# M2S-v2-Modular.net
KiCad netlist of a schematic drawn in EAGLE
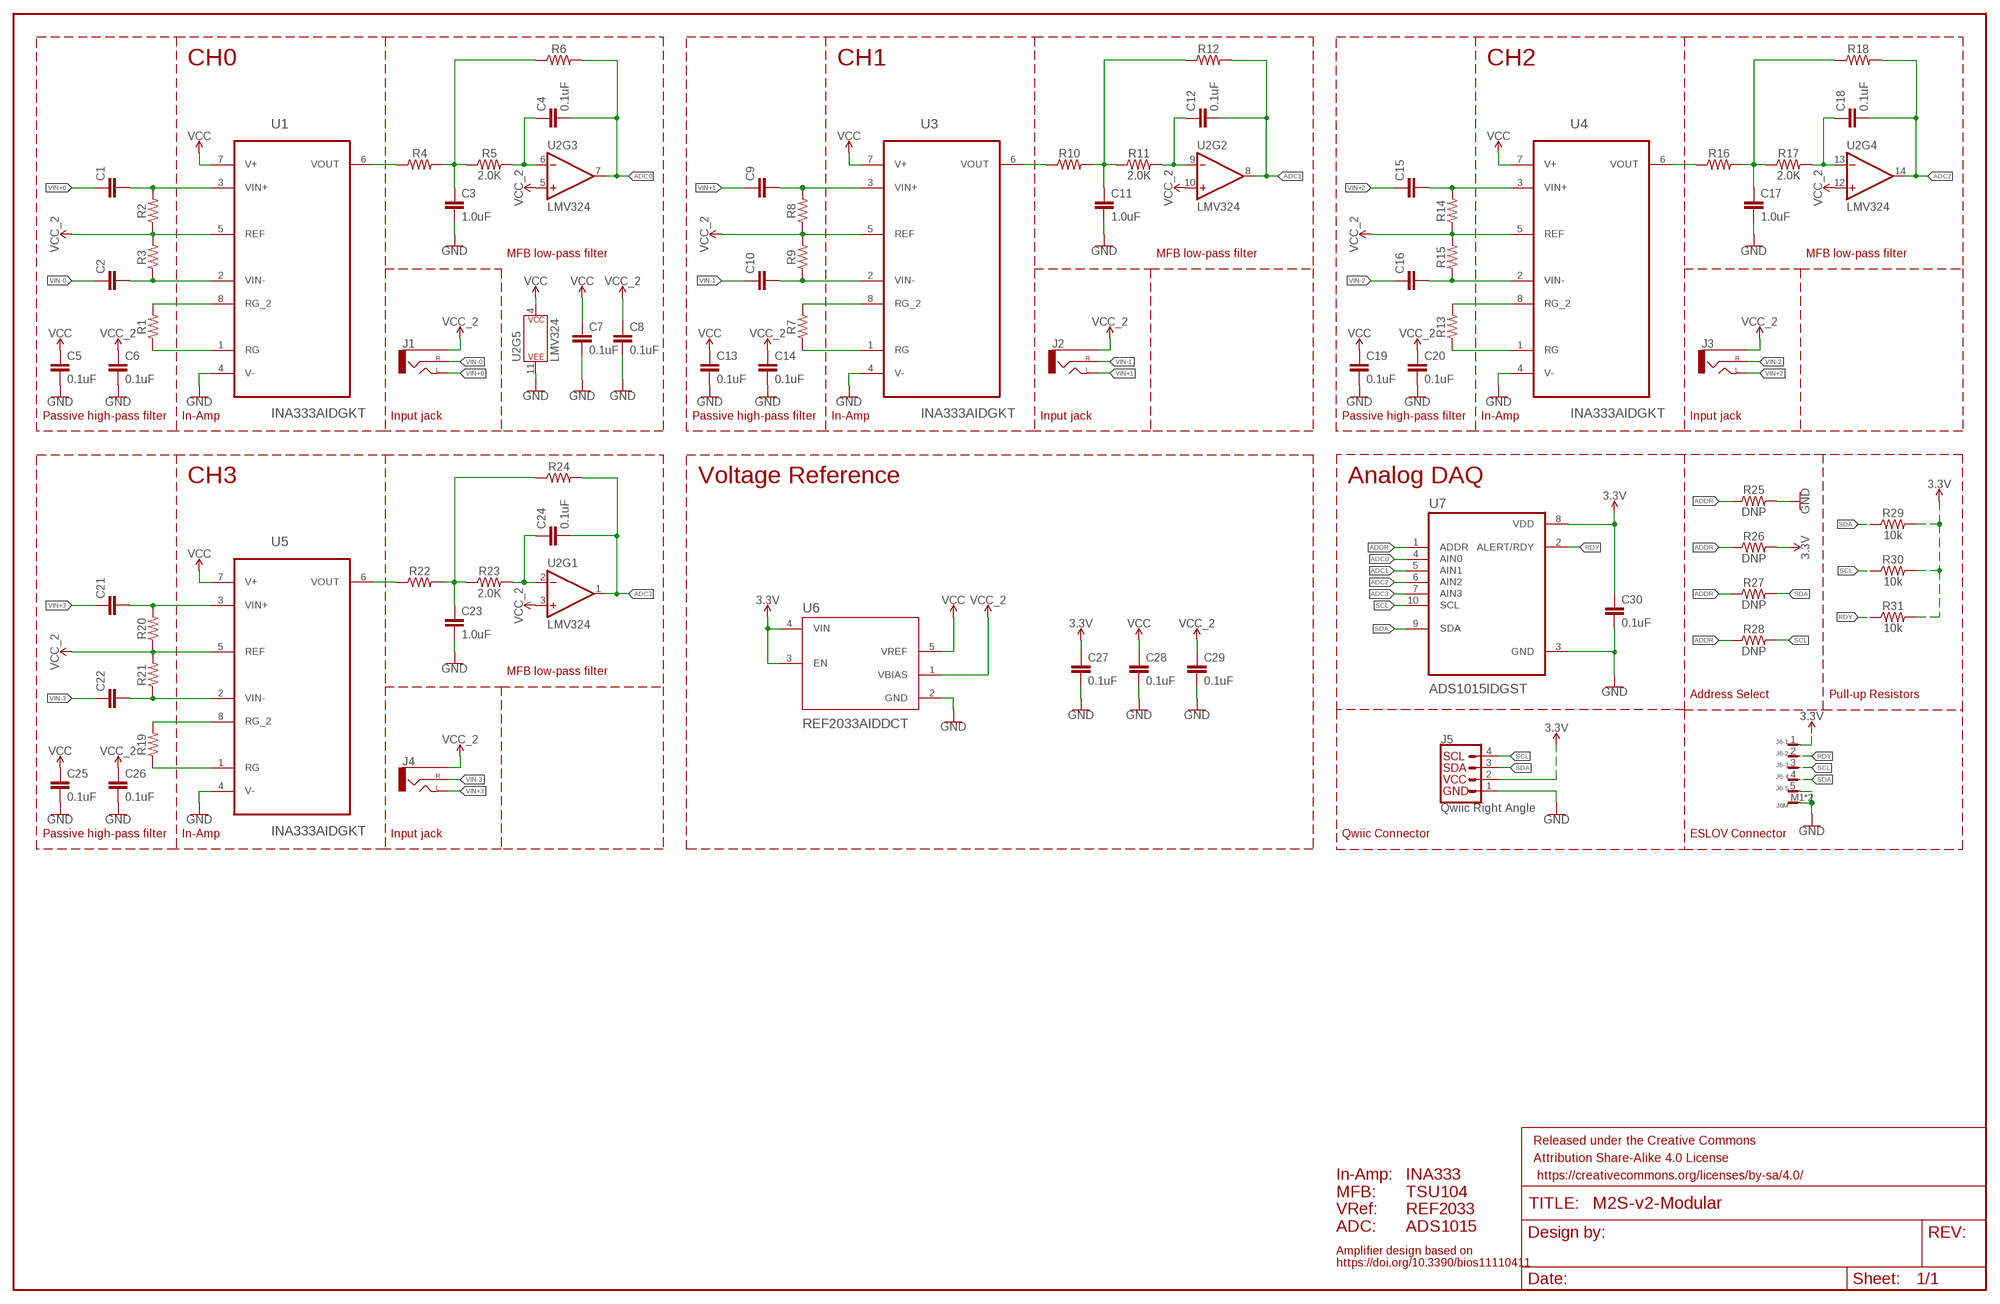
[diagram p0: schematic, sheet 1]

(export (version "E")
  (design (tool "Eeschema 10.0.6"))
  (components
    (comp (ref "C1")
      (value "0.22uF")
      (footprint "eagle-import:0402")
      (libsource (lib "eagle-import") (part "CAP-0402"))
    )
    (comp (ref "C2")
      (value "0.22uF")
      (footprint "eagle-import:0402")
      (libsource (lib "eagle-import") (part "CAP-0402"))
    )
    (comp (ref "C3")
      (value "1.0uF")
      (footprint "eagle-import:0402")
      (libsource (lib "eagle-import") (part "1.0UF-0402-16V-10%"))
    )
    (comp (ref "C4")
      (value "0.1uF")
      (footprint "eagle-import:0402")
      (libsource (lib "eagle-import") (part "0.1UF-0402-6.3V-10%-X7R"))
    )
    (comp (ref "C5")
      (value "0.1uF")
      (footprint "eagle-import:0402")
      (libsource (lib "eagle-import") (part "0.1UF-0402-6.3V-10%-X7R"))
    )
    (comp (ref "C6")
      (value "0.1uF")
      (footprint "eagle-import:0402")
      (libsource (lib "eagle-import") (part "0.1UF-0402-6.3V-10%-X7R"))
    )
    (comp (ref "C7")
      (value "0.1uF")
      (footprint "eagle-import:0402")
      (libsource (lib "eagle-import") (part "0.1UF-0402-6.3V-10%-X7R"))
    )
    (comp (ref "C8")
      (value "0.1uF")
      (footprint "eagle-import:0402")
      (libsource (lib "eagle-import") (part "0.1UF-0402-6.3V-10%-X7R"))
    )
    (comp (ref "C9")
      (value "0.22uF")
      (footprint "eagle-import:0402")
      (libsource (lib "eagle-import") (part "CAP-0402"))
    )
    (comp (ref "C10")
      (value "0.22uF")
      (footprint "eagle-import:0402")
      (libsource (lib "eagle-import") (part "CAP-0402"))
    )
    (comp (ref "C11")
      (value "1.0uF")
      (footprint "eagle-import:0402")
      (libsource (lib "eagle-import") (part "1.0UF-0402-16V-10%"))
    )
    (comp (ref "C12")
      (value "0.1uF")
      (footprint "eagle-import:0402")
      (libsource (lib "eagle-import") (part "0.1UF-0402-6.3V-10%-X7R"))
    )
    (comp (ref "C13")
      (value "0.1uF")
      (footprint "eagle-import:0402")
      (libsource (lib "eagle-import") (part "0.1UF-0402-6.3V-10%-X7R"))
    )
    (comp (ref "C14")
      (value "0.1uF")
      (footprint "eagle-import:0402")
      (libsource (lib "eagle-import") (part "0.1UF-0402-6.3V-10%-X7R"))
    )
    (comp (ref "C15")
      (value "0.22uF")
      (footprint "eagle-import:0402")
      (libsource (lib "eagle-import") (part "CAP-0402"))
    )
    (comp (ref "C16")
      (value "0.22uF")
      (footprint "eagle-import:0402")
      (libsource (lib "eagle-import") (part "CAP-0402"))
    )
    (comp (ref "C17")
      (value "1.0uF")
      (footprint "eagle-import:0402")
      (libsource (lib "eagle-import") (part "1.0UF-0402-16V-10%"))
    )
    (comp (ref "C18")
      (value "0.1uF")
      (footprint "eagle-import:0402")
      (libsource (lib "eagle-import") (part "0.1UF-0402-6.3V-10%-X7R"))
    )
    (comp (ref "C19")
      (value "0.1uF")
      (footprint "eagle-import:0402")
      (libsource (lib "eagle-import") (part "0.1UF-0402-6.3V-10%-X7R"))
    )
    (comp (ref "C20")
      (value "0.1uF")
      (footprint "eagle-import:0402")
      (libsource (lib "eagle-import") (part "0.1UF-0402-6.3V-10%-X7R"))
    )
    (comp (ref "C21")
      (value "0.22uF")
      (footprint "eagle-import:0402")
      (libsource (lib "eagle-import") (part "CAP-0402"))
    )
    (comp (ref "C22")
      (value "0.22uF")
      (footprint "eagle-import:0402")
      (libsource (lib "eagle-import") (part "CAP-0402"))
    )
    (comp (ref "C23")
      (value "1.0uF")
      (footprint "eagle-import:0402")
      (libsource (lib "eagle-import") (part "1.0UF-0402-16V-10%"))
    )
    (comp (ref "C24")
      (value "0.1uF")
      (footprint "eagle-import:0402")
      (libsource (lib "eagle-import") (part "0.1UF-0402-6.3V-10%-X7R"))
    )
    (comp (ref "C25")
      (value "0.1uF")
      (footprint "eagle-import:0402")
      (libsource (lib "eagle-import") (part "0.1UF-0402-6.3V-10%-X7R"))
    )
    (comp (ref "C26")
      (value "0.1uF")
      (footprint "eagle-import:0402")
      (libsource (lib "eagle-import") (part "0.1UF-0402-6.3V-10%-X7R"))
    )
    (comp (ref "C27")
      (value "0.1uF")
      (footprint "eagle-import:0402")
      (libsource (lib "eagle-import") (part "0.1UF-0402-6.3V-10%-X7R"))
    )
    (comp (ref "C28")
      (value "0.1uF")
      (footprint "eagle-import:0402")
      (libsource (lib "eagle-import") (part "0.1UF-0402-6.3V-10%-X7R"))
    )
    (comp (ref "C29")
      (value "0.1uF")
      (footprint "eagle-import:0402")
      (libsource (lib "eagle-import") (part "0.1UF-0402-6.3V-10%-X7R"))
    )
    (comp (ref "C30")
      (value "0.1uF")
      (footprint "eagle-import:0402")
      (libsource (lib "eagle-import") (part "0.1UF-0402-6.3V-10%-X7R"))
    )
    (comp (ref "FRAME1")
      (value "FRAME-LEDGERNO_FOOTPRINT")
      (footprint "eagle-import:DUMMY")
      (libsource (lib "eagle-import") (part "FRAME-LEDGERNO_FOOTPRINT"))
    )
    (comp (ref "J1")
      (value "AUDIO_JACK_2.5MM_2.5MM")
      (footprint "eagle-import:STEREOJACK2.5MM_STEREOJACK2.5MM")
      (libsource (lib "eagle-import") (part "AUDIO_JACK_2.5MM_2.5MM"))
    )
    (comp (ref "J2")
      (value "AUDIO_JACK_2.5MM_2.5MM")
      (footprint "eagle-import:STEREOJACK2.5MM_STEREOJACK2.5MM")
      (libsource (lib "eagle-import") (part "AUDIO_JACK_2.5MM_2.5MM"))
    )
    (comp (ref "J3")
      (value "AUDIO_JACK_2.5MM_2.5MM")
      (footprint "eagle-import:STEREOJACK2.5MM_STEREOJACK2.5MM")
      (libsource (lib "eagle-import") (part "AUDIO_JACK_2.5MM_2.5MM"))
    )
    (comp (ref "J4")
      (value "AUDIO_JACK_2.5MM_2.5MM")
      (footprint "eagle-import:STEREOJACK2.5MM_STEREOJACK2.5MM")
      (libsource (lib "eagle-import") (part "AUDIO_JACK_2.5MM_2.5MM"))
    )
    (comp (ref "J5")
      (value "Qwiic Right Angle")
      (footprint "eagle-import:JST04_1MM_RA")
      (libsource (lib "eagle-import") (part "I2C_STANDARDQWIIC"))
    )
    (comp (ref "J6")
      (value "SM05B-SRSS-TB")
      (footprint "eagle-import:SM05B-SRSS-TB")
      (libsource (lib "eagle-import") (part "SM05B-SRSS-TB"))
    )
    (comp (ref "R1")
      (value "1KOHM-0402-1/16W-1%")
      (footprint "eagle-import:0402")
      (libsource (lib "eagle-import") (part "1KOHM-0402-1/16W-1%"))
    )
    (comp (ref "R2")
      (value "RESISTOR0402")
      (footprint "eagle-import:0402")
      (libsource (lib "eagle-import") (part "RESISTOR0402"))
    )
    (comp (ref "R3")
      (value "RESISTOR0402")
      (footprint "eagle-import:0402")
      (libsource (lib "eagle-import") (part "RESISTOR0402"))
    )
    (comp (ref "R4")
      (value "RESISTOR0402")
      (footprint "eagle-import:0402")
      (libsource (lib "eagle-import") (part "RESISTOR0402"))
    )
    (comp (ref "R5")
      (value "2.0K")
      (footprint "eagle-import:0402")
      (libsource (lib "eagle-import") (part "2.0KOHM-0402-1/16W-1%"))
    )
    (comp (ref "R6")
      (value "RESISTOR0402")
      (footprint "eagle-import:0402")
      (libsource (lib "eagle-import") (part "RESISTOR0402"))
    )
    (comp (ref "R7")
      (value "1KOHM-0402-1/16W-1%")
      (footprint "eagle-import:0402")
      (libsource (lib "eagle-import") (part "1KOHM-0402-1/16W-1%"))
    )
    (comp (ref "R8")
      (value "RESISTOR0402")
      (footprint "eagle-import:0402")
      (libsource (lib "eagle-import") (part "RESISTOR0402"))
    )
    (comp (ref "R9")
      (value "RESISTOR0402")
      (footprint "eagle-import:0402")
      (libsource (lib "eagle-import") (part "RESISTOR0402"))
    )
    (comp (ref "R10")
      (value "RESISTOR0402")
      (footprint "eagle-import:0402")
      (libsource (lib "eagle-import") (part "RESISTOR0402"))
    )
    (comp (ref "R11")
      (value "2.0K")
      (footprint "eagle-import:0402")
      (libsource (lib "eagle-import") (part "2.0KOHM-0402-1/16W-1%"))
    )
    (comp (ref "R12")
      (value "RESISTOR0402")
      (footprint "eagle-import:0402")
      (libsource (lib "eagle-import") (part "RESISTOR0402"))
    )
    (comp (ref "R13")
      (value "1KOHM-0402-1/16W-1%")
      (footprint "eagle-import:0402")
      (libsource (lib "eagle-import") (part "1KOHM-0402-1/16W-1%"))
    )
    (comp (ref "R14")
      (value "RESISTOR0402")
      (footprint "eagle-import:0402")
      (libsource (lib "eagle-import") (part "RESISTOR0402"))
    )
    (comp (ref "R15")
      (value "RESISTOR0402")
      (footprint "eagle-import:0402")
      (libsource (lib "eagle-import") (part "RESISTOR0402"))
    )
    (comp (ref "R16")
      (value "RESISTOR0402")
      (footprint "eagle-import:0402")
      (libsource (lib "eagle-import") (part "RESISTOR0402"))
    )
    (comp (ref "R17")
      (value "2.0K")
      (footprint "eagle-import:0402")
      (libsource (lib "eagle-import") (part "2.0KOHM-0402-1/16W-1%"))
    )
    (comp (ref "R18")
      (value "RESISTOR0402")
      (footprint "eagle-import:0402")
      (libsource (lib "eagle-import") (part "RESISTOR0402"))
    )
    (comp (ref "R19")
      (value "1KOHM-0402-1/16W-1%")
      (footprint "eagle-import:0402")
      (libsource (lib "eagle-import") (part "1KOHM-0402-1/16W-1%"))
    )
    (comp (ref "R20")
      (value "RESISTOR0402")
      (footprint "eagle-import:0402")
      (libsource (lib "eagle-import") (part "RESISTOR0402"))
    )
    (comp (ref "R21")
      (value "RESISTOR0402")
      (footprint "eagle-import:0402")
      (libsource (lib "eagle-import") (part "RESISTOR0402"))
    )
    (comp (ref "R22")
      (value "RESISTOR0402")
      (footprint "eagle-import:0402")
      (libsource (lib "eagle-import") (part "RESISTOR0402"))
    )
    (comp (ref "R23")
      (value "2.0K")
      (footprint "eagle-import:0402")
      (libsource (lib "eagle-import") (part "2.0KOHM-0402-1/16W-1%"))
    )
    (comp (ref "R24")
      (value "RESISTOR0402")
      (footprint "eagle-import:0402")
      (libsource (lib "eagle-import") (part "RESISTOR0402"))
    )
    (comp (ref "R25")
      (value "DNP")
      (footprint "eagle-import:0402")
      (libsource (lib "eagle-import") (part "DNP-0402"))
    )
    (comp (ref "R26")
      (value "DNP")
      (footprint "eagle-import:0402")
      (libsource (lib "eagle-import") (part "DNP-0402"))
    )
    (comp (ref "R27")
      (value "DNP")
      (footprint "eagle-import:0402")
      (libsource (lib "eagle-import") (part "DNP-0402"))
    )
    (comp (ref "R28")
      (value "DNP")
      (footprint "eagle-import:0402")
      (libsource (lib "eagle-import") (part "DNP-0402"))
    )
    (comp (ref "R29")
      (value "10k")
      (footprint "eagle-import:0402")
      (libsource (lib "eagle-import") (part "10KOHM-0402-1/16W-1%"))
    )
    (comp (ref "R30")
      (value "10k")
      (footprint "eagle-import:0402")
      (libsource (lib "eagle-import") (part "10KOHM-0402-1/16W-1%"))
    )
    (comp (ref "R31")
      (value "10k")
      (footprint "eagle-import:0402")
      (libsource (lib "eagle-import") (part "10KOHM-0402-1/16W-1%"))
    )
    (comp (ref "U1")
      (value "INA333AIDGKT")
      (footprint "eagle-import:SOP65P490X110-8N")
      (libsource (lib "eagle-import") (part "INA333AIDGKT"))
    )
    (comp (ref "U2")
      (value "LMV324")
      (footprint "eagle-import:SO14")
      (libsource (lib "eagle-import") (part "LMV324"))
    )
    (comp (ref "U3")
      (value "INA333AIDGKT")
      (footprint "eagle-import:SOP65P490X110-8N")
      (libsource (lib "eagle-import") (part "INA333AIDGKT"))
    )
    (comp (ref "U4")
      (value "INA333AIDGKT")
      (footprint "eagle-import:SOP65P490X110-8N")
      (libsource (lib "eagle-import") (part "INA333AIDGKT"))
    )
    (comp (ref "U5")
      (value "INA333AIDGKT")
      (footprint "eagle-import:SOP65P490X110-8N")
      (libsource (lib "eagle-import") (part "INA333AIDGKT"))
    )
    (comp (ref "U6")
      (value "REF2033AIDDCT")
      (footprint "eagle-import:SOT95P280X110-5N")
      (fields (field (name "MF") "Texas Instruments"))
      (libsource (lib "eagle-import") (part "REF2033AIDDCT"))
    )
    (comp (ref "U7")
      (value "ADS1015IDGST")
      (footprint "eagle-import:SOP50P490X110-10N")
      (fields (field (name "MF") "Texas Instruments"))
      (libsource (lib "eagle-import") (part "ADS1015IDGST"))
    )
  )
  (nets
    (net (code "1") (name "3.3V") (class "Default")
      (node (ref "C27") (pin "1") (pinfunction "1_1") (pintype "passive"))
      (node (ref "C30") (pin "1") (pinfunction "1_1") (pintype "passive"))
      (node (ref "J5") (pin "2") (pinfunction "2_2") (pintype "power_in"))
      (node (ref "J6") (pin "1") (pinfunction "P_1") (pintype "bidirectional"))
      (node (ref "R26") (pin "2") (pinfunction "2_2") (pintype "passive"))
      (node (ref "R29") (pin "2") (pinfunction "2_2") (pintype "passive"))
      (node (ref "R30") (pin "2") (pinfunction "2_2") (pintype "passive"))
      (node (ref "R31") (pin "2") (pinfunction "2_2") (pintype "passive"))
      (node (ref "U6") (pin "3") (pinfunction "EN_3") (pintype "input"))
      (node (ref "U6") (pin "4") (pinfunction "VIN_4") (pintype "power_in"))
      (node (ref "U7") (pin "8") (pinfunction "VDD_8") (pintype "power_in"))
    )
    (net (code "2") (name "ADC0") (class "Default")
      (node (ref "C4") (pin "2") (pinfunction "2_2") (pintype "passive"))
      (node (ref "R6") (pin "2") (pinfunction "2_2") (pintype "passive"))
      (node (ref "U2") (pin "7") (pinfunction "OUT_7") (pintype "output"))
      (node (ref "U7") (pin "4") (pinfunction "AIN0_4") (pintype "input"))
    )
    (net (code "3") (name "ADC1") (class "Default")
      (node (ref "C12") (pin "2") (pinfunction "2_2") (pintype "passive"))
      (node (ref "R12") (pin "2") (pinfunction "2_2") (pintype "passive"))
      (node (ref "U2") (pin "8") (pinfunction "OUT_8") (pintype "output"))
      (node (ref "U7") (pin "5") (pinfunction "AIN1_5") (pintype "input"))
    )
    (net (code "4") (name "ADC2") (class "Default")
      (node (ref "C18") (pin "2") (pinfunction "2_2") (pintype "passive"))
      (node (ref "R18") (pin "2") (pinfunction "2_2") (pintype "passive"))
      (node (ref "U2") (pin "14") (pinfunction "OUT_14") (pintype "output"))
      (node (ref "U7") (pin "6") (pinfunction "AIN2_6") (pintype "input"))
    )
    (net (code "5") (name "ADC3") (class "Default")
      (node (ref "C24") (pin "2") (pinfunction "2_2") (pintype "passive"))
      (node (ref "R24") (pin "2") (pinfunction "2_2") (pintype "passive"))
      (node (ref "U2") (pin "1") (pinfunction "OUT_1") (pintype "output"))
      (node (ref "U7") (pin "7") (pinfunction "AIN3_7") (pintype "input"))
    )
    (net (code "6") (name "ADDR") (class "Default")
      (node (ref "R25") (pin "1") (pinfunction "1_1") (pintype "passive"))
      (node (ref "R26") (pin "1") (pinfunction "1_1") (pintype "passive"))
      (node (ref "R27") (pin "1") (pinfunction "1_1") (pintype "passive"))
      (node (ref "R28") (pin "1") (pinfunction "1_1") (pintype "passive"))
      (node (ref "U7") (pin "1") (pinfunction "ADDR_1") (pintype "input"))
    )
    (net (code "7") (name "GND") (class "Default")
      (node (ref "C11") (pin "2") (pinfunction "2_2") (pintype "passive"))
      (node (ref "C13") (pin "2") (pinfunction "2_2") (pintype "passive"))
      (node (ref "C14") (pin "2") (pinfunction "2_2") (pintype "passive"))
      (node (ref "C17") (pin "2") (pinfunction "2_2") (pintype "passive"))
      (node (ref "C19") (pin "2") (pinfunction "2_2") (pintype "passive"))
      (node (ref "C20") (pin "2") (pinfunction "2_2") (pintype "passive"))
      (node (ref "C23") (pin "2") (pinfunction "2_2") (pintype "passive"))
      (node (ref "C25") (pin "2") (pinfunction "2_2") (pintype "passive"))
      (node (ref "C26") (pin "2") (pinfunction "2_2") (pintype "passive"))
      (node (ref "C27") (pin "2") (pinfunction "2_2") (pintype "passive"))
      (node (ref "C28") (pin "2") (pinfunction "2_2") (pintype "passive"))
      (node (ref "C29") (pin "2") (pinfunction "2_2") (pintype "passive"))
      (node (ref "C3") (pin "2") (pinfunction "2_2") (pintype "passive"))
      (node (ref "C30") (pin "2") (pinfunction "2_2") (pintype "passive"))
      (node (ref "C5") (pin "2") (pinfunction "2_2") (pintype "passive"))
      (node (ref "C6") (pin "2") (pinfunction "2_2") (pintype "passive"))
      (node (ref "C7") (pin "2") (pinfunction "2_2") (pintype "passive"))
      (node (ref "C8") (pin "2") (pinfunction "2_2") (pintype "passive"))
      (node (ref "J5") (pin "1") (pinfunction "1_1") (pintype "power_in"))
      (node (ref "J6") (pin "5") (pinfunction "P_5") (pintype "bidirectional"))
      (node (ref "J6") (pin "M1") (pinfunction "P_M1") (pintype "bidirectional"))
      (node (ref "J6") (pin "M2") (pinfunction "P_M2") (pintype "bidirectional"))
      (node (ref "R25") (pin "2") (pinfunction "2_2") (pintype "passive"))
      (node (ref "U1") (pin "4") (pinfunction "V-_4") (pintype "power_in"))
      (node (ref "U2") (pin "11") (pinfunction "P$V-_11") (pintype "bidirectional"))
      (node (ref "U3") (pin "4") (pinfunction "V-_4") (pintype "power_in"))
      (node (ref "U4") (pin "4") (pinfunction "V-_4") (pintype "power_in"))
      (node (ref "U5") (pin "4") (pinfunction "V-_4") (pintype "power_in"))
      (node (ref "U6") (pin "2") (pinfunction "GND_2") (pintype "power_in"))
      (node (ref "U7") (pin "3") (pinfunction "GND_3") (pintype "power_in"))
    )
    (net (code "8") (name "Net-(C3-Pad1)") (class "Default")
      (node (ref "C3") (pin "1") (pinfunction "1_1") (pintype "passive"))
      (node (ref "R4") (pin "2") (pinfunction "2_2") (pintype "passive"))
      (node (ref "R5") (pin "1") (pinfunction "1_1") (pintype "passive"))
      (node (ref "R6") (pin "1") (pinfunction "1_1") (pintype "passive"))
    )
    (net (code "9") (name "Net-(C11-Pad1)") (class "Default")
      (node (ref "C11") (pin "1") (pinfunction "1_1") (pintype "passive"))
      (node (ref "R10") (pin "2") (pinfunction "2_2") (pintype "passive"))
      (node (ref "R11") (pin "1") (pinfunction "1_1") (pintype "passive"))
      (node (ref "R12") (pin "1") (pinfunction "1_1") (pintype "passive"))
    )
    (net (code "10") (name "Net-(C17-Pad1)") (class "Default")
      (node (ref "C17") (pin "1") (pinfunction "1_1") (pintype "passive"))
      (node (ref "R16") (pin "2") (pinfunction "2_2") (pintype "passive"))
      (node (ref "R17") (pin "1") (pinfunction "1_1") (pintype "passive"))
      (node (ref "R18") (pin "1") (pinfunction "1_1") (pintype "passive"))
    )
    (net (code "11") (name "Net-(C23-Pad1)") (class "Default")
      (node (ref "C23") (pin "1") (pinfunction "1_1") (pintype "passive"))
      (node (ref "R22") (pin "2") (pinfunction "2_2") (pintype "passive"))
      (node (ref "R23") (pin "1") (pinfunction "1_1") (pintype "passive"))
      (node (ref "R24") (pin "1") (pinfunction "1_1") (pintype "passive"))
    )
    (net (code "12") (name "Net-(U1-RG)") (class "Default")
      (node (ref "R1") (pin "1") (pinfunction "1_1") (pintype "passive"))
      (node (ref "U1") (pin "1") (pinfunction "RG_1") (pintype "passive"))
    )
    (net (code "13") (name "Net-(U1-RG_2)") (class "Default")
      (node (ref "R1") (pin "2") (pinfunction "2_2") (pintype "passive"))
      (node (ref "U1") (pin "8") (pinfunction "RG_2_8") (pintype "passive"))
    )
    (net (code "14") (name "Net-(U1-VIN+)") (class "Default")
      (node (ref "C1") (pin "2") (pinfunction "2_2") (pintype "passive"))
      (node (ref "R2") (pin "2") (pinfunction "2_2") (pintype "passive"))
      (node (ref "U1") (pin "3") (pinfunction "VIN+_3") (pintype "input"))
    )
    (net (code "15") (name "Net-(U1-VIN-)") (class "Default")
      (node (ref "C2") (pin "2") (pinfunction "2_2") (pintype "passive"))
      (node (ref "R3") (pin "1") (pinfunction "1_1") (pintype "passive"))
      (node (ref "U1") (pin "2") (pinfunction "VIN-_2") (pintype "input"))
    )
    (net (code "16") (name "Net-(U1-VOUT)") (class "Default")
      (node (ref "R4") (pin "1") (pinfunction "1_1") (pintype "passive"))
      (node (ref "U1") (pin "6") (pinfunction "VOUT_6") (pintype "output"))
    )
    (net (code "17") (name "Net-(U2A--IN)") (class "Default")
      (node (ref "C24") (pin "1") (pinfunction "1_1") (pintype "passive"))
      (node (ref "R23") (pin "2") (pinfunction "2_2") (pintype "passive"))
      (node (ref "U2") (pin "2") (pinfunction "-IN_2") (pintype "input"))
    )
    (net (code "18") (name "Net-(U2B--IN)") (class "Default")
      (node (ref "C12") (pin "1") (pinfunction "1_1") (pintype "passive"))
      (node (ref "R11") (pin "2") (pinfunction "2_2") (pintype "passive"))
      (node (ref "U2") (pin "9") (pinfunction "-IN_9") (pintype "input"))
    )
    (net (code "19") (name "Net-(U2C--IN)") (class "Default")
      (node (ref "C4") (pin "1") (pinfunction "1_1") (pintype "passive"))
      (node (ref "R5") (pin "2") (pinfunction "2_2") (pintype "passive"))
      (node (ref "U2") (pin "6") (pinfunction "-IN_6") (pintype "input"))
    )
    (net (code "20") (name "Net-(U2D--IN)") (class "Default")
      (node (ref "C18") (pin "1") (pinfunction "1_1") (pintype "passive"))
      (node (ref "R17") (pin "2") (pinfunction "2_2") (pintype "passive"))
      (node (ref "U2") (pin "13") (pinfunction "-IN_13") (pintype "input"))
    )
    (net (code "21") (name "Net-(U3-RG)") (class "Default")
      (node (ref "R7") (pin "1") (pinfunction "1_1") (pintype "passive"))
      (node (ref "U3") (pin "1") (pinfunction "RG_1") (pintype "passive"))
    )
    (net (code "22") (name "Net-(U3-RG_2)") (class "Default")
      (node (ref "R7") (pin "2") (pinfunction "2_2") (pintype "passive"))
      (node (ref "U3") (pin "8") (pinfunction "RG_2_8") (pintype "passive"))
    )
    (net (code "23") (name "Net-(U3-VIN+)") (class "Default")
      (node (ref "C9") (pin "2") (pinfunction "2_2") (pintype "passive"))
      (node (ref "R8") (pin "2") (pinfunction "2_2") (pintype "passive"))
      (node (ref "U3") (pin "3") (pinfunction "VIN+_3") (pintype "input"))
    )
    (net (code "24") (name "Net-(U3-VIN-)") (class "Default")
      (node (ref "C10") (pin "2") (pinfunction "2_2") (pintype "passive"))
      (node (ref "R9") (pin "1") (pinfunction "1_1") (pintype "passive"))
      (node (ref "U3") (pin "2") (pinfunction "VIN-_2") (pintype "input"))
    )
    (net (code "25") (name "Net-(U3-VOUT)") (class "Default")
      (node (ref "R10") (pin "1") (pinfunction "1_1") (pintype "passive"))
      (node (ref "U3") (pin "6") (pinfunction "VOUT_6") (pintype "output"))
    )
    (net (code "26") (name "Net-(U4-RG)") (class "Default")
      (node (ref "R13") (pin "1") (pinfunction "1_1") (pintype "passive"))
      (node (ref "U4") (pin "1") (pinfunction "RG_1") (pintype "passive"))
    )
    (net (code "27") (name "Net-(U4-RG_2)") (class "Default")
      (node (ref "R13") (pin "2") (pinfunction "2_2") (pintype "passive"))
      (node (ref "U4") (pin "8") (pinfunction "RG_2_8") (pintype "passive"))
    )
    (net (code "28") (name "Net-(U4-VIN+)") (class "Default")
      (node (ref "C15") (pin "2") (pinfunction "2_2") (pintype "passive"))
      (node (ref "R14") (pin "2") (pinfunction "2_2") (pintype "passive"))
      (node (ref "U4") (pin "3") (pinfunction "VIN+_3") (pintype "input"))
    )
    (net (code "29") (name "Net-(U4-VIN-)") (class "Default")
      (node (ref "C16") (pin "2") (pinfunction "2_2") (pintype "passive"))
      (node (ref "R15") (pin "1") (pinfunction "1_1") (pintype "passive"))
      (node (ref "U4") (pin "2") (pinfunction "VIN-_2") (pintype "input"))
    )
    (net (code "30") (name "Net-(U4-VOUT)") (class "Default")
      (node (ref "R16") (pin "1") (pinfunction "1_1") (pintype "passive"))
      (node (ref "U4") (pin "6") (pinfunction "VOUT_6") (pintype "output"))
    )
    (net (code "31") (name "Net-(U5-RG)") (class "Default")
      (node (ref "R19") (pin "1") (pinfunction "1_1") (pintype "passive"))
      (node (ref "U5") (pin "1") (pinfunction "RG_1") (pintype "passive"))
    )
    (net (code "32") (name "Net-(U5-RG_2)") (class "Default")
      (node (ref "R19") (pin "2") (pinfunction "2_2") (pintype "passive"))
      (node (ref "U5") (pin "8") (pinfunction "RG_2_8") (pintype "passive"))
    )
    (net (code "33") (name "Net-(U5-VIN+)") (class "Default")
      (node (ref "C21") (pin "2") (pinfunction "2_2") (pintype "passive"))
      (node (ref "R20") (pin "2") (pinfunction "2_2") (pintype "passive"))
      (node (ref "U5") (pin "3") (pinfunction "VIN+_3") (pintype "input"))
    )
    (net (code "34") (name "Net-(U5-VIN-)") (class "Default")
      (node (ref "C22") (pin "2") (pinfunction "2_2") (pintype "passive"))
      (node (ref "R21") (pin "1") (pinfunction "1_1") (pintype "passive"))
      (node (ref "U5") (pin "2") (pinfunction "VIN-_2") (pintype "input"))
    )
    (net (code "35") (name "Net-(U5-VOUT)") (class "Default")
      (node (ref "R22") (pin "1") (pinfunction "1_1") (pintype "passive"))
      (node (ref "U5") (pin "6") (pinfunction "VOUT_6") (pintype "output"))
    )
    (net (code "36") (name "RDY") (class "Default")
      (node (ref "J6") (pin "2") (pinfunction "P_2") (pintype "bidirectional"))
      (node (ref "R31") (pin "1") (pinfunction "1_1") (pintype "passive"))
      (node (ref "U7") (pin "2") (pinfunction "ALERT/RDY_2") (pintype "output"))
    )
    (net (code "37") (name "SCL") (class "Default")
      (node (ref "J5") (pin "4") (pinfunction "4_4") (pintype "passive"))
      (node (ref "J6") (pin "3") (pinfunction "P_3") (pintype "bidirectional"))
      (node (ref "R28") (pin "2") (pinfunction "2_2") (pintype "passive"))
      (node (ref "R30") (pin "1") (pinfunction "1_1") (pintype "passive"))
      (node (ref "U7") (pin "10") (pinfunction "SCL_10") (pintype "input"))
    )
    (net (code "38") (name "SDA") (class "Default")
      (node (ref "J5") (pin "3") (pinfunction "3_3") (pintype "passive"))
      (node (ref "J6") (pin "4") (pinfunction "P_4") (pintype "bidirectional"))
      (node (ref "R27") (pin "2") (pinfunction "2_2") (pintype "passive"))
      (node (ref "R29") (pin "1") (pinfunction "1_1") (pintype "passive"))
      (node (ref "U7") (pin "9") (pinfunction "SDA_9") (pintype "bidirectional"))
    )
    (net (code "39") (name "VCC") (class "Default")
      (node (ref "C13") (pin "1") (pinfunction "1_1") (pintype "passive"))
      (node (ref "C19") (pin "1") (pinfunction "1_1") (pintype "passive"))
      (node (ref "C25") (pin "1") (pinfunction "1_1") (pintype "passive"))
      (node (ref "C28") (pin "1") (pinfunction "1_1") (pintype "passive"))
      (node (ref "C5") (pin "1") (pinfunction "1_1") (pintype "passive"))
      (node (ref "C7") (pin "1") (pinfunction "1_1") (pintype "passive"))
      (node (ref "U1") (pin "7") (pinfunction "V+_7") (pintype "power_in"))
      (node (ref "U2") (pin "4") (pinfunction "P$V+_4") (pintype "bidirectional"))
      (node (ref "U3") (pin "7") (pinfunction "V+_7") (pintype "power_in"))
      (node (ref "U4") (pin "7") (pinfunction "V+_7") (pintype "power_in"))
      (node (ref "U5") (pin "7") (pinfunction "V+_7") (pintype "power_in"))
      (node (ref "U6") (pin "5") (pinfunction "VREF_5") (pintype "output"))
    )
    (net (code "40") (name "VCC_2") (class "Default")
      (node (ref "C14") (pin "1") (pinfunction "1_1") (pintype "passive"))
      (node (ref "C20") (pin "1") (pinfunction "1_1") (pintype "passive"))
      (node (ref "C26") (pin "1") (pinfunction "1_1") (pintype "passive"))
      (node (ref "C29") (pin "1") (pinfunction "1_1") (pintype "passive"))
      (node (ref "C6") (pin "1") (pinfunction "1_1") (pintype "passive"))
      (node (ref "C8") (pin "1") (pinfunction "1_1") (pintype "passive"))
      (node (ref "J1") (pin "RING1") (pinfunction "SLEEVE_RING1") (pintype "bidirectional"))
      (node (ref "J2") (pin "RING1") (pinfunction "SLEEVE_RING1") (pintype "bidirectional"))
      (node (ref "J3") (pin "RING1") (pinfunction "SLEEVE_RING1") (pintype "bidirectional"))
      (node (ref "J4") (pin "RING1") (pinfunction "SLEEVE_RING1") (pintype "bidirectional"))
      (node (ref "R14") (pin "1") (pinfunction "1_1") (pintype "passive"))
      (node (ref "R15") (pin "2") (pinfunction "2_2") (pintype "passive"))
      (node (ref "R2") (pin "1") (pinfunction "1_1") (pintype "passive"))
      (node (ref "R20") (pin "1") (pinfunction "1_1") (pintype "passive"))
      (node (ref "R21") (pin "2") (pinfunction "2_2") (pintype "passive"))
      (node (ref "R3") (pin "2") (pinfunction "2_2") (pintype "passive"))
      (node (ref "R8") (pin "1") (pinfunction "1_1") (pintype "passive"))
      (node (ref "R9") (pin "2") (pinfunction "2_2") (pintype "passive"))
      (node (ref "U1") (pin "5") (pinfunction "REF_5") (pintype "input"))
      (node (ref "U2") (pin "10") (pinfunction "+IN_10") (pintype "input"))
      (node (ref "U2") (pin "12") (pinfunction "+IN_12") (pintype "input"))
      (node (ref "U2") (pin "3") (pinfunction "+IN_3") (pintype "input"))
      (node (ref "U2") (pin "5") (pinfunction "+IN_5") (pintype "input"))
      (node (ref "U3") (pin "5") (pinfunction "REF_5") (pintype "input"))
      (node (ref "U4") (pin "5") (pinfunction "REF_5") (pintype "input"))
      (node (ref "U5") (pin "5") (pinfunction "REF_5") (pintype "input"))
      (node (ref "U6") (pin "1") (pinfunction "VBIAS_1") (pintype "output"))
    )
    (net (code "41") (name "VIN+0") (class "Default")
      (node (ref "C1") (pin "1") (pinfunction "1_1") (pintype "passive"))
      (node (ref "J1") (pin "SHIELD") (pinfunction "LEFT_SHIELD") (pintype "bidirectional"))
    )
    (net (code "42") (name "VIN+1") (class "Default")
      (node (ref "C9") (pin "1") (pinfunction "1_1") (pintype "passive"))
      (node (ref "J2") (pin "SHIELD") (pinfunction "LEFT_SHIELD") (pintype "bidirectional"))
    )
    (net (code "43") (name "VIN+2") (class "Default")
      (node (ref "C15") (pin "1") (pinfunction "1_1") (pintype "passive"))
      (node (ref "J3") (pin "SHIELD") (pinfunction "LEFT_SHIELD") (pintype "bidirectional"))
    )
    (net (code "44") (name "VIN+3") (class "Default")
      (node (ref "C21") (pin "1") (pinfunction "1_1") (pintype "passive"))
      (node (ref "J4") (pin "SHIELD") (pinfunction "LEFT_SHIELD") (pintype "bidirectional"))
    )
    (net (code "45") (name "VIN-0") (class "Default")
      (node (ref "C2") (pin "1") (pinfunction "1_1") (pintype "passive"))
      (node (ref "J1") (pin "TIP") (pinfunction "RIGHT_TIP") (pintype "bidirectional"))
    )
    (net (code "46") (name "VIN-1") (class "Default")
      (node (ref "C10") (pin "1") (pinfunction "1_1") (pintype "passive"))
      (node (ref "J2") (pin "TIP") (pinfunction "RIGHT_TIP") (pintype "bidirectional"))
    )
    (net (code "47") (name "VIN-2") (class "Default")
      (node (ref "C16") (pin "1") (pinfunction "1_1") (pintype "passive"))
      (node (ref "J3") (pin "TIP") (pinfunction "RIGHT_TIP") (pintype "bidirectional"))
    )
    (net (code "48") (name "VIN-3") (class "Default")
      (node (ref "C22") (pin "1") (pinfunction "1_1") (pintype "passive"))
      (node (ref "J4") (pin "TIP") (pinfunction "RIGHT_TIP") (pintype "bidirectional"))
    )
  )
)
